# Power.net
KiCad netlist of a schematic drawn in Altium Designer
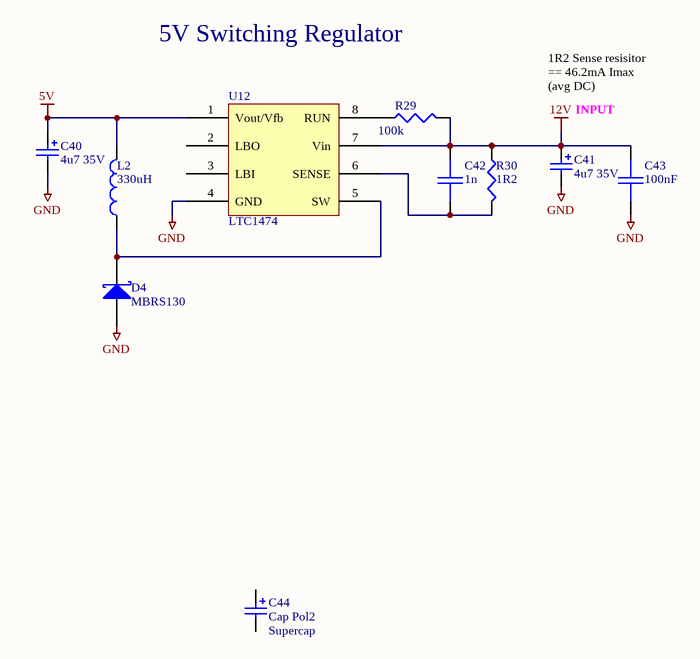
[diagram p0: Power.SchDoc]

(export (version "E")
  (design (tool "Eeschema 10.0.6"))
  (components
    (comp (ref "C40")
      (value "4u7 35V")
      (footprint "MCCT-CASEC")
      (description "Polarized Capacitor (Surface Mount)")
      (libsource (lib "Miscellaneous Devices") (part "Cap Pol3"))
    )
    (comp (ref "C41")
      (value "4u7 35V")
      (footprint "MCCT-CASEC")
      (description "Polarized Capacitor (Surface Mount)")
      (libsource (lib "Miscellaneous Devices") (part "Cap Pol3"))
    )
    (comp (ref "C42")
      (value "1n")
      (footprint "0603")
      (description "Capacitor")
      (libsource (lib "Miscellaneous Devices") (part "CAP"))
    )
    (comp (ref "C43")
      (value "100nF")
      (footprint "0603")
      (description "Capacitor")
      (libsource (lib "Miscellaneous Devices") (part "CAP"))
    )
    (comp (ref "C44")
      (value "Cap Pol2")
      (footprint "CAPPA14.05-10.5x6.3")
      (description "Polarized Capacitor (Axial)")
      (fields (field (name "ALTIUM_VALUE") "Supercap") (field (name "PUBLISHER") "Altium Limited"))
      (libsource (lib "Miscellaneous Devices") (part "Cap Pol2"))
    )
    (comp (ref "D4")
      (value "MBRS130")
      (footprint "SMB")
      (description "Schottky Diode")
      (libsource (lib "RCLDQ") (part "D SCHOTTKY"))
    )
    (comp (ref "L2")
      (value "330uH")
      (footprint "1812")
      (description "Inductor")
      (libsource (lib "Miscellaneous Devices") (part "Inductor"))
    )
    (comp (ref "R29")
      (value "100k")
      (footprint "0603")
      (description "Resistor")
      (libsource (lib "RCLDQ") (part "RES1"))
    )
    (comp (ref "R30")
      (value "1R2")
      (footprint "0603")
      (description "Resistor")
      (libsource (lib "Miscellaneous Devices") (part "RES1"))
    )
    (comp (ref "U12")
      (value "LTC1474")
      (footprint "TSOP8")
      (description "Step-down converter")
      (libsource (lib "MiscellaneousIC") (part "LTC1474"))
    )
  )
  (nets
    (net (code "1") (name "5V") (class "Default")
      (node (ref "C40") (pin "1") (pinfunction "1_1") (pintype "passive"))
      (node (ref "L2") (pin "2") (pinfunction "2_2") (pintype "passive"))
      (node (ref "U12") (pin "1") (pinfunction "Vout/Vfb_1") (pintype "passive"))
    )
    (net (code "2") (name "12V") (class "Default")
      (node (ref "C41") (pin "1") (pinfunction "1_1") (pintype "passive"))
      (node (ref "C42") (pin "1") (pinfunction "1_1") (pintype "passive"))
      (node (ref "C43") (pin "1") (pinfunction "1_1") (pintype "passive"))
      (node (ref "R29") (pin "2") (pinfunction "2_2") (pintype "passive"))
      (node (ref "R30") (pin "1") (pinfunction "1_1") (pintype "passive"))
      (node (ref "U12") (pin "7") (pinfunction "Vin_7") (pintype "passive"))
    )
    (net (code "3") (name "GND") (class "Default")
      (node (ref "C40") (pin "2") (pinfunction "2_2") (pintype "passive"))
      (node (ref "C41") (pin "2") (pinfunction "2_2") (pintype "passive"))
      (node (ref "C43") (pin "2") (pinfunction "2_2") (pintype "passive"))
      (node (ref "D4") (pin "A") (pinfunction "A_A") (pintype "passive"))
      (node (ref "U12") (pin "4") (pinfunction "GND_4") (pintype "passive"))
    )
    (net (code "4") (name "Net-(U12-RUN)") (class "Default")
      (node (ref "R29") (pin "1") (pinfunction "1_1") (pintype "passive"))
      (node (ref "U12") (pin "8") (pinfunction "RUN_8") (pintype "passive"))
    )
    (net (code "5") (name "Net-(U12-SENSE)") (class "Default")
      (node (ref "C42") (pin "2") (pinfunction "2_2") (pintype "passive"))
      (node (ref "R30") (pin "2") (pinfunction "2_2") (pintype "passive"))
      (node (ref "U12") (pin "6") (pinfunction "SENSE_6") (pintype "passive"))
    )
    (net (code "6") (name "Net-(U12-SW)") (class "Default")
      (node (ref "D4") (pin "K") (pinfunction "K_K") (pintype "passive"))
      (node (ref "L2") (pin "1") (pinfunction "1_1") (pintype "passive"))
      (node (ref "U12") (pin "5") (pinfunction "SW_5") (pintype "passive"))
    )
    (net (code "7") (name "unconnected-(C44-Pad1)") (class "Default")
      (node (ref "C44") (pin "1") (pinfunction "1_1") (pintype "passive"))
    )
    (net (code "8") (name "unconnected-(C44-Pad2)") (class "Default")
      (node (ref "C44") (pin "2") (pinfunction "2_2") (pintype "passive"))
    )
    (net (code "9") (name "unconnected-(U12-LBI-Pad3)") (class "Default")
      (node (ref "U12") (pin "3") (pinfunction "LBI_3") (pintype "passive"))
    )
    (net (code "10") (name "unconnected-(U12-LBO-Pad2)") (class "Default")
      (node (ref "U12") (pin "2") (pinfunction "LBO_2") (pintype "passive"))
    )
  )
)
